# MAIN.net
KiCad netlist of a schematic drawn in Altium Designer
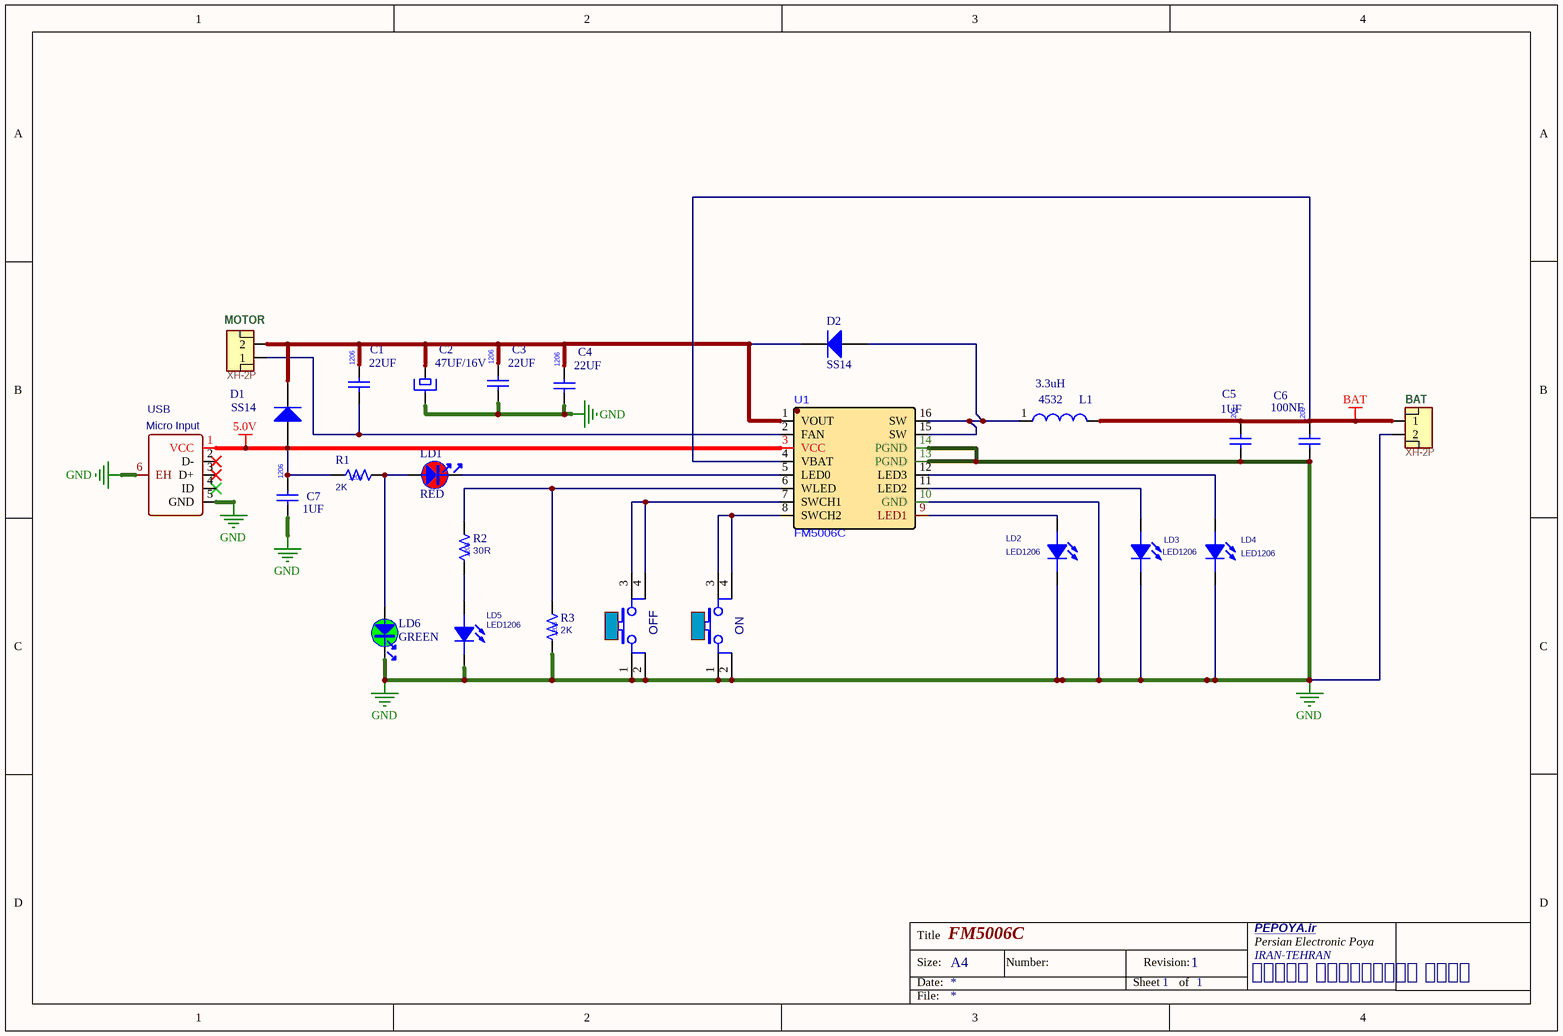
[diagram p0: MAIN.SchDoc]

(export (version "E")
  (design (tool "Eeschema 10.0.6"))
  (components
    (comp (ref "BAT")
      (value "XH-2P")
      (footprint "XHB-2AW")
      (description "=Description")
      (libsource (lib "") (part "JST-2_1"))
    )
    (comp (ref "C1")
      (value "22UF")
      (footprint "Cap1206 - duplicate")
      (fields (field (name "MANUFACTURER PART NUMBER") "1206 100nF"))
      (libsource (lib "02_R&C") (part "C_1206"))
    )
    (comp (ref "C2")
      (value "47UF/16V")
      (footprint "WCAP-AS5H 5x5.5x1.4")
      (description "3.3uF 400V")
      (fields (field (name "MANUFACTURER") "Wurth") (field (name "MANUFACTURER PART NUMBER") "860021373005"))
      (libsource (lib "altium-import") (part "root_0_EKRG250ETD101MF09D_"))
    )
    (comp (ref "C3")
      (value "22UF")
      (footprint "Cap1206 - duplicate")
      (fields (field (name "MANUFACTURER PART NUMBER") "1206 100nF"))
      (libsource (lib "02_R&C") (part "C_1206"))
    )
    (comp (ref "C4")
      (value "22UF")
      (footprint "Cap1206 - duplicate")
      (fields (field (name "MANUFACTURER PART NUMBER") "1206 100nF"))
      (libsource (lib "02_R&C") (part "C_1206"))
    )
    (comp (ref "C5")
      (value "1UF")
      (footprint "Cap1206 - duplicate")
      (fields (field (name "MANUFACTURER PART NUMBER") "1206 100nF"))
      (libsource (lib "02_R&C") (part "C_1206"))
    )
    (comp (ref "C6")
      (value "100NF")
      (footprint "Cap1206 - duplicate")
      (fields (field (name "MANUFACTURER PART NUMBER") "1206 100nF"))
      (libsource (lib "02_R&C") (part "C_1206"))
    )
    (comp (ref "C7")
      (value "1UF")
      (footprint "Cap1206 - duplicate")
      (fields (field (name "MANUFACTURER PART NUMBER") "1206 100nF"))
      (libsource (lib "02_R&C") (part "C_1206"))
    )
    (comp (ref "D1")
      (value "SS14")
      (footprint "Diode 1N4007 SMD")
      (description "High Conductance Fast Diode")
      (fields (field (name "PUBLISHER") "SJ Unlimited") (field (name "DESIGNER") "Eng. Saeid Jorablo"))
      (libsource (lib "General_06 Passive Components") (part "DIODE_1N4148"))
    )
    (comp (ref "D2")
      (value "SS14")
      (footprint "Diode 1N4007 SMD")
      (description "High Conductance Fast Diode")
      (fields (field (name "PUBLISHER") "SJ Unlimited") (field (name "DESIGNER") "Eng. Saeid Jorablo"))
      (libsource (lib "General_06 Passive Components") (part "DIODE_1N4148"))
    )
    (comp (ref "L1")
      (value "3.3uH")
      (footprint "Inductor 4532")
      (description "1mH 0.43A DR0608")
      (fields (field (name "MANUFACTURER") "BOURNS") (field (name "MANUFACTURER PART NUMBER") "4532"))
      (libsource (lib "altium-import") (part "root_0_DR0608-105L_"))
    )
    (comp (ref "LD1")
      (value "RED")
      (footprint "LED 1206")
      (description "LED, Red, VF : Min=1.75V , Max=2.35V, 25mA, 0603")
      (fields (field (name "INTERNAL_PART_NUMBER") "MCD-02899") (field (name "MANUFACTURER") "EVERLIGHT"))
      (libsource (lib "MCD_PARTS_database") (part "LED_red"))
    )
    (comp (ref "LD2")
      (value "LED1206")
      (footprint "LED 1206")
      (description "Light Emitting Diode")
      (fields (field (name "DESIGNER") "Abbas Basereh"))
      (libsource (lib "Schematic") (part "LED 5MM"))
    )
    (comp (ref "LD3")
      (value "LED1206")
      (footprint "LED 1206")
      (description "Light Emitting Diode")
      (fields (field (name "DESIGNER") "Abbas Basereh"))
      (libsource (lib "Schematic") (part "LED 5MM"))
    )
    (comp (ref "LD4")
      (value "LED1206")
      (footprint "LED 1206")
      (description "Light Emitting Diode")
      (fields (field (name "DESIGNER") "Abbas Basereh"))
      (libsource (lib "Schematic") (part "LED 5MM"))
    )
    (comp (ref "LD5")
      (value "LED1206")
      (footprint "LED 1206")
      (description "Light Emitting Diode")
      (fields (field (name "DESIGNER") "Abbas Basereh"))
      (libsource (lib "Schematic") (part "LED 5MM"))
    )
    (comp (ref "LD6")
      (value "GREEN")
      (footprint "LED 1206")
      (description "LED, Green, 2V, 25mA, 0603, SMD")
      (fields (field (name "INTERNAL_PART_NUMBER") "MCD-02900") (field (name "MANUFACTURER") "EVERLIGHT"))
      (libsource (lib "MCD_PARTS_database") (part "LED_green"))
    )
    (comp (ref "MOTOR")
      (value "XH-2P")
      (footprint "XHB-2AW")
      (description "=Description")
      (libsource (lib "JST-2") (part "JST-2"))
    )
    (comp (ref "OFF")
      (value "SW-PUSH-CMS_BLUE")
      (footprint "431471031826")
      (description "Non-Open Push-Button 0.1A 24V BLUE")
      (fields
        (field (name "INTERNAL_PART_NUMBER") "MCD-00002")
        (field (name "MANUFACTURER") "WEALTHMETAL")
        (field (name "PROVIDED_BY") "Subcon")
      )
      (libsource (lib "MCD_PARTS_database") (part "SW-PUSH-CMS_BLUE"))
    )
    (comp (ref "ON")
      (value "SW-PUSH-CMS_BLUE")
      (footprint "431471031826")
      (description "Non-Open Push-Button 0.1A 24V BLUE")
      (fields
        (field (name "INTERNAL_PART_NUMBER") "MCD-00002")
        (field (name "MANUFACTURER") "WEALTHMETAL")
        (field (name "PROVIDED_BY") "Subcon")
      )
      (libsource (lib "MCD_PARTS_database") (part "SW-PUSH-CMS_BLUE"))
    )
    (comp (ref "R1") (value "2K") (footprint "RES1206") (libsource (lib "02_R&C") (part "R_1206")))
    (comp (ref "R2") (value "30R") (footprint "RES1206") (libsource (lib "02_R&C") (part "R_1206")))
    (comp (ref "R3") (value "2K") (footprint "RES1206") (libsource (lib "02_R&C") (part "R_1206")))
    (comp (ref "U1")
      (value "FM5006C")
      (footprint "SOP-16")
      (description "SO-16")
      (libsource (lib "FM5006c") (part "FM5006C"))
    )
    (comp (ref "USB")
      (value "Micro Input")
      (footprint "USB MICRO")
      (fields
        (field (name "MANUFACTURER") "XKB Enterprise")
        (field (name "MANUFACTURER PART") "U254-051T-4BH23-S2B")
        (field (name "CONTRIBUTOR") "LCSC")
      )
      (libsource (lib "altium-import") (part "root_0_Micro Input_"))
    )
  )
  (nets
    (net (code "1") (name "5.0V") (class "Default")
      (node (ref "C7") (pin "1") (pinfunction "1_1") (pintype "passive"))
      (node (ref "D1") (pin "1") (pinfunction "A_1") (pintype "passive"))
      (node (ref "R1") (pin "1") (pinfunction "1_1") (pintype "passive"))
      (node (ref "U1") (pin "3") (pinfunction "VCC_3") (pintype "passive"))
      (node (ref "USB") (pin "1") (pinfunction "VCC_1") (pintype "passive"))
    )
    (net (code "2") (name "BAT") (class "Default")
      (node (ref "BAT") (pin "1") (pinfunction "1_1") (pintype "passive"))
      (node (ref "C5") (pin "1") (pinfunction "1_1") (pintype "passive"))
      (node (ref "C6") (pin "1") (pinfunction "1_1") (pintype "passive"))
      (node (ref "L1") (pin "2") (pinfunction "2_2") (pintype "passive"))
      (node (ref "U1") (pin "4") (pinfunction "VBAT_4") (pintype "passive"))
    )
    (net (code "3") (name "GND") (class "Default")
      (node (ref "BAT") (pin "2") (pinfunction "2_2") (pintype "passive"))
      (node (ref "C2") (pin "2") (pinfunction "2_2") (pintype "passive"))
      (node (ref "C3") (pin "2") (pinfunction "2_2") (pintype "passive"))
      (node (ref "C4") (pin "2") (pinfunction "2_2") (pintype "passive"))
      (node (ref "C5") (pin "2") (pinfunction "2_2") (pintype "passive"))
      (node (ref "C6") (pin "2") (pinfunction "2_2") (pintype "passive"))
      (node (ref "C7") (pin "2") (pinfunction "2_2") (pintype "passive"))
      (node (ref "LD2") (pin "2") (pinfunction "CATHODE_2") (pintype "passive"))
      (node (ref "LD3") (pin "2") (pinfunction "CATHODE_2") (pintype "passive"))
      (node (ref "LD4") (pin "2") (pinfunction "CATHODE_2") (pintype "passive"))
      (node (ref "LD5") (pin "2") (pinfunction "CATHODE_2") (pintype "passive"))
      (node (ref "LD6") (pin "2") (pintype "passive"))
      (node (ref "OFF") (pin "1") (pinfunction "1_1") (pintype "passive"))
      (node (ref "OFF") (pin "2") (pinfunction "2_2") (pintype "passive"))
      (node (ref "ON") (pin "1") (pinfunction "1_1") (pintype "passive"))
      (node (ref "ON") (pin "2") (pinfunction "2_2") (pintype "passive"))
      (node (ref "R3") (pin "1") (pinfunction "1_1") (pintype "passive"))
      (node (ref "U1") (pin "10") (pinfunction "GND_10") (pintype "passive"))
      (node (ref "U1") (pin "13") (pinfunction "PGND_13") (pintype "passive"))
      (node (ref "U1") (pin "14") (pinfunction "PGND_14") (pintype "passive"))
      (node (ref "USB") (pin "5") (pinfunction "GND_5") (pintype "passive"))
      (node (ref "USB") (pin "6") (pinfunction "EH_6") (pintype "passive"))
    )
    (net (code "4") (name "Net-(D1-K)") (class "Default")
      (node (ref "C1") (pin "1") (pinfunction "1_1") (pintype "passive"))
      (node (ref "C2") (pin "1") (pinfunction "1_1") (pintype "passive"))
      (node (ref "C3") (pin "1") (pinfunction "1_1") (pintype "passive"))
      (node (ref "C4") (pin "1") (pinfunction "1_1") (pintype "passive"))
      (node (ref "D1") (pin "2") (pinfunction "K_2") (pintype "passive"))
      (node (ref "D2") (pin "2") (pinfunction "K_2") (pintype "passive"))
      (node (ref "MOTOR") (pin "2") (pinfunction "2_2") (pintype "passive"))
      (node (ref "U1") (pin "1") (pinfunction "VOUT_1") (pintype "passive"))
    )
    (net (code "5") (name "Net-(D2-A)") (class "Default")
      (node (ref "D2") (pin "1") (pinfunction "A_1") (pintype "passive"))
      (node (ref "L1") (pin "1") (pinfunction "1_1") (pintype "passive"))
      (node (ref "U1") (pin "15") (pinfunction "SW_15") (pintype "passive"))
      (node (ref "U1") (pin "16") (pinfunction "SW_16") (pintype "passive"))
    )
    (net (code "6") (name "Net-(LD1-Pad1)") (class "Default")
      (node (ref "LD1") (pin "1") (pintype "passive"))
      (node (ref "LD6") (pin "1") (pintype "passive"))
      (node (ref "R1") (pin "2") (pinfunction "2_2") (pintype "passive"))
    )
    (net (code "7") (name "Net-(LD2-ANODE)") (class "Default")
      (node (ref "LD2") (pin "1") (pinfunction "ANODE_1") (pintype "passive"))
      (node (ref "U1") (pin "9") (pinfunction "LED1_9") (pintype "passive"))
    )
    (net (code "8") (name "Net-(LD3-ANODE)") (class "Default")
      (node (ref "LD3") (pin "1") (pinfunction "ANODE_1") (pintype "passive"))
      (node (ref "U1") (pin "11") (pinfunction "LED2_11") (pintype "passive"))
    )
    (net (code "9") (name "Net-(LD4-ANODE)") (class "Default")
      (node (ref "LD4") (pin "1") (pinfunction "ANODE_1") (pintype "passive"))
      (node (ref "U1") (pin "12") (pinfunction "LED3_12") (pintype "passive"))
    )
    (net (code "10") (name "Net-(LD5-ANODE)") (class "Default")
      (node (ref "LD5") (pin "1") (pinfunction "ANODE_1") (pintype "passive"))
      (node (ref "R2") (pin "1") (pinfunction "1_1") (pintype "passive"))
    )
    (net (code "11") (name "Net-(U1-FAN)") (class "Default")
      (node (ref "C1") (pin "2") (pinfunction "2_2") (pintype "passive"))
      (node (ref "MOTOR") (pin "1") (pinfunction "1_1") (pintype "passive"))
      (node (ref "U1") (pin "2") (pinfunction "FAN_2") (pintype "passive"))
    )
    (net (code "12") (name "Net-(U1-LED0)") (class "Default")
      (node (ref "LD1") (pin "2") (pintype "passive"))
      (node (ref "U1") (pin "5") (pinfunction "LED0_5") (pintype "passive"))
    )
    (net (code "13") (name "Net-(U1-SWCH1)") (class "Default")
      (node (ref "OFF") (pin "3") (pinfunction "3_3") (pintype "passive"))
      (node (ref "OFF") (pin "4") (pinfunction "4_4") (pintype "passive"))
      (node (ref "U1") (pin "7") (pinfunction "SWCH1_7") (pintype "passive"))
    )
    (net (code "14") (name "Net-(U1-SWCH2)") (class "Default")
      (node (ref "ON") (pin "3") (pinfunction "3_3") (pintype "passive"))
      (node (ref "ON") (pin "4") (pinfunction "4_4") (pintype "passive"))
      (node (ref "U1") (pin "8") (pinfunction "SWCH2_8") (pintype "passive"))
    )
    (net (code "15") (name "Net-(U1-WLED)") (class "Default")
      (node (ref "R2") (pin "2") (pinfunction "2_2") (pintype "passive"))
      (node (ref "R3") (pin "2") (pinfunction "2_2") (pintype "passive"))
      (node (ref "U1") (pin "6") (pinfunction "WLED_6") (pintype "passive"))
    )
    (net (code "16") (name "unconnected-(USB-D+-Pad3)") (class "Default")
      (node (ref "USB") (pin "3") (pinfunction "D+_3") (pintype "passive+no_connect"))
    )
    (net (code "17") (name "unconnected-(USB-D--Pad2)") (class "Default")
      (node (ref "USB") (pin "2") (pinfunction "D-_2") (pintype "passive+no_connect"))
    )
    (net (code "18") (name "unconnected-(USB-ID-Pad4)") (class "Default")
      (node (ref "USB") (pin "4") (pinfunction "ID_4") (pintype "passive+no_connect"))
    )
  )
)
